# modul_zasilania.net
KiCad netlist of a schematic drawn in EAGLE
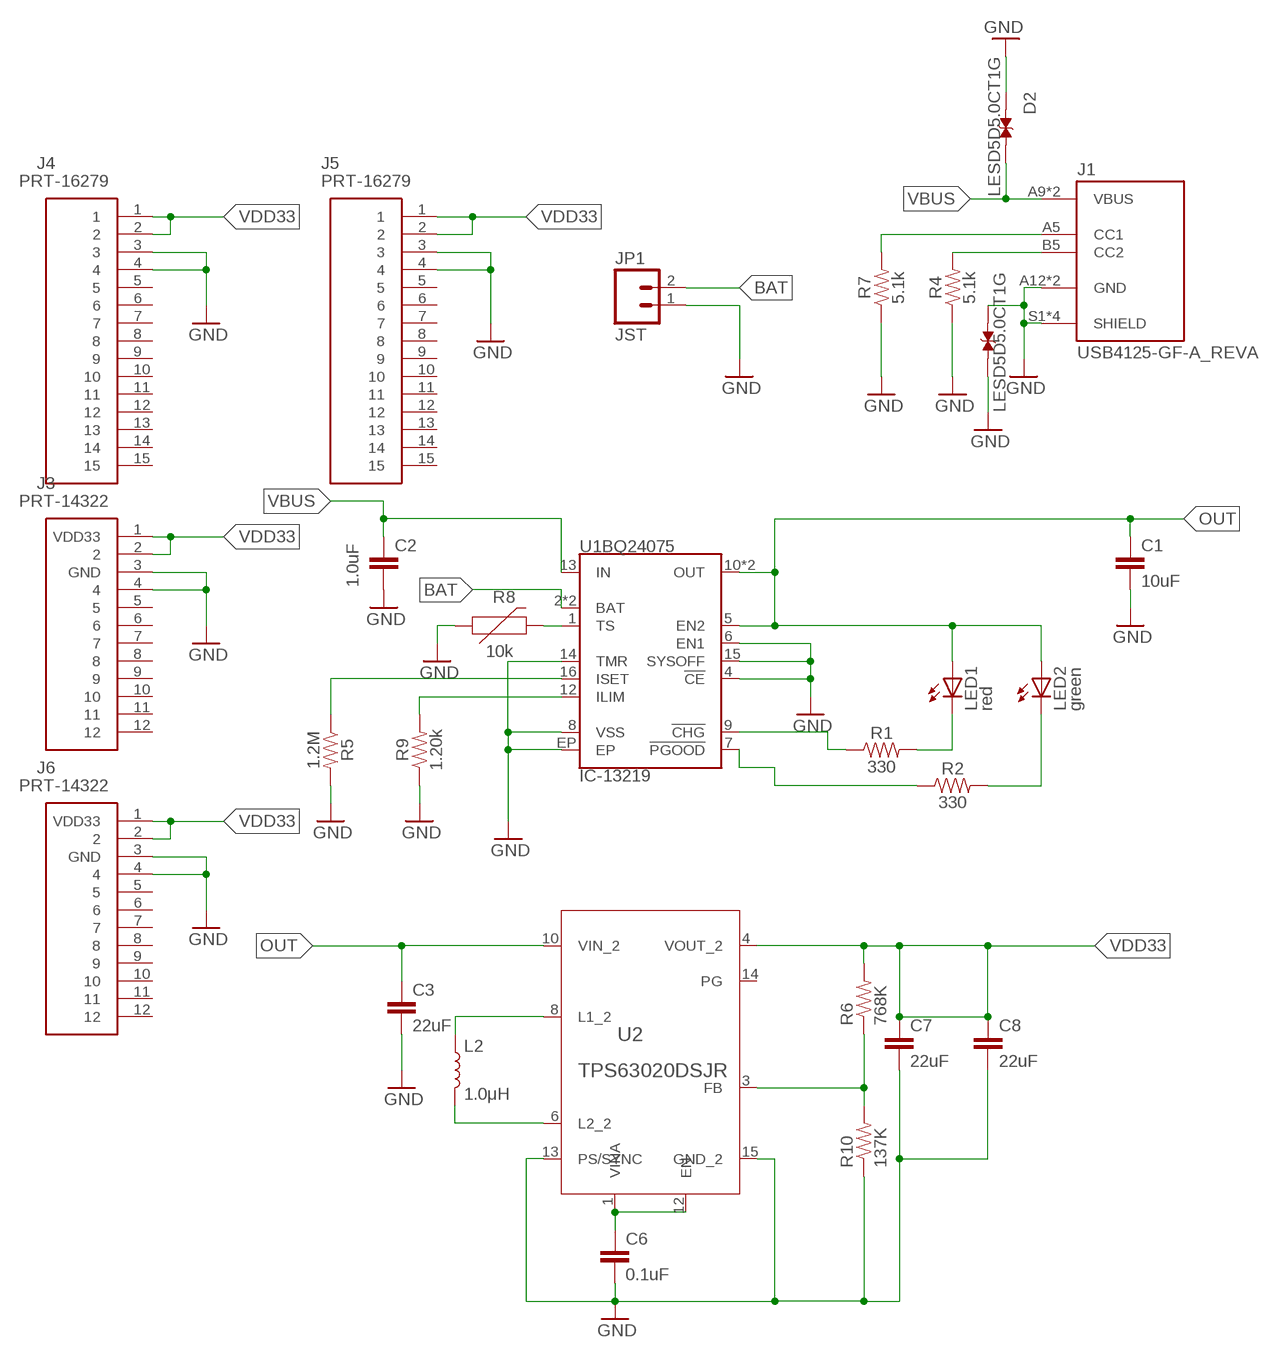
[diagram p0: schematic, sheet 1]

(export (version "E")
  (design (tool "Eeschema 10.0.6"))
  (components
    (comp (ref "C1")
      (value "10uF")
      (footprint "eagle-import:1206")
      (libsource (lib "eagle-import") (part "10UF-1206-6.3V-20%"))
    )
    (comp (ref "C2")
      (value "1.0uF")
      (footprint "eagle-import:0603")
      (libsource (lib "eagle-import") (part "1.0UF-0603-16V-10%"))
    )
    (comp (ref "C3")
      (value "22uF")
      (footprint "eagle-import:0603")
      (libsource (lib "eagle-import") (part "22UF-0603-6.3V-20%"))
    )
    (comp (ref "C6")
      (value "0.1uF")
      (footprint "eagle-import:0402")
      (libsource (lib "eagle-import") (part "0.1UF-0402-16V-10%"))
    )
    (comp (ref "C7")
      (value "22uF")
      (footprint "eagle-import:0603")
      (libsource (lib "eagle-import") (part "22UF-0603-6.3V-20%"))
    )
    (comp (ref "C8")
      (value "22uF")
      (footprint "eagle-import:0603")
      (libsource (lib "eagle-import") (part "22UF-0603-6.3V-20%"))
    )
    (comp (ref "D1")
      (value "LESD5D5.0CT1G")
      (footprint "eagle-import:TVS_LESD5D5.0CT1G")
      (fields (field (name "MF") "Leshan Radio Co."))
      (libsource (lib "eagle-import") (part "LESD5D5.0CT1G"))
    )
    (comp (ref "D2")
      (value "LESD5D5.0CT1G")
      (footprint "eagle-import:TVS_LESD5D5.0CT1G")
      (fields (field (name "MF") "Leshan Radio Co."))
      (libsource (lib "eagle-import") (part "LESD5D5.0CT1G"))
    )
    (comp (ref "J1")
      (value "USB4125-GF-A_REVA")
      (footprint "eagle-import:GCT_USB4125-GF-A_REVA")
      (fields (field (name "MF") "Global Connector Technology") (field (name "MP") "USB4125-GF-A"))
      (libsource (lib "eagle-import") (part "USB4125-GF-A_REVA"))
    )
    (comp (ref "J3")
      (value "PRT-14322")
      (footprint "eagle-import:RHDR12W87P0X254_1X12_3103X250X")
      (fields (field (name "MOUSER_PART_NUMBER") "474-PRT-14322"))
      (libsource (lib "eagle-import") (part "PRT-14322"))
    )
    (comp (ref "J4")
      (value "PRT-16279")
      (footprint "eagle-import:PRT16279")
      (fields (field (name "MOUSER_PART_NUMBER") "474-PRT-16279"))
      (libsource (lib "eagle-import") (part "PRT-16279"))
    )
    (comp (ref "J5")
      (value "PRT-16279")
      (footprint "eagle-import:PRT16279")
      (fields (field (name "MOUSER_PART_NUMBER") "474-PRT-16279"))
      (libsource (lib "eagle-import") (part "PRT-16279"))
    )
    (comp (ref "J6")
      (value "PRT-14322")
      (footprint "eagle-import:RHDR12W87P0X254_1X12_3103X250X")
      (fields (field (name "MOUSER_PART_NUMBER") "474-PRT-14322"))
      (libsource (lib "eagle-import") (part "PRT-14322"))
    )
    (comp (ref "JP1")
      (value "JST")
      (footprint "eagle-import:JST-2-SMD")
      (libsource (lib "eagle-import") (part "M02-JST-2MM-SMT"))
    )
    (comp (ref "L2")
      (value "1.0μH")
      (footprint "eagle-import:0805-WIDE")
      (libsource (lib "eagle-import") (part "1.0μH-0805_WIDE-1.0μH-1.4A-0.07OHM-1.4MM_H"))
    )
    (comp (ref "LED1")
      (value "red")
      (footprint "eagle-import:CHIP-LED0805")
      (libsource (lib "eagle-import") (part "LEDCHIP-LED0805"))
    )
    (comp (ref "LED2")
      (value "green")
      (footprint "eagle-import:CHIP-LED0805")
      (libsource (lib "eagle-import") (part "LEDCHIP-LED0805"))
    )
    (comp (ref "R1")
      (value "330")
      (footprint "eagle-import:0603")
      (libsource (lib "eagle-import") (part "330OHM-0603-1/10W-1%"))
    )
    (comp (ref "R2")
      (value "330")
      (footprint "eagle-import:0603")
      (libsource (lib "eagle-import") (part "330OHM-0603-1/10W-1%"))
    )
    (comp (ref "R4")
      (value "5.1k")
      (footprint "eagle-import:0603")
      (libsource (lib "eagle-import") (part "5.1KOHM5.1KOHM-0603-1/10W-1%"))
    )
    (comp (ref "R5")
      (value "1.2M")
      (footprint "eagle-import:0603")
      (libsource (lib "eagle-import") (part "1.2MOHM-0603-1/10W-1%"))
    )
    (comp (ref "R6")
      (value "768K")
      (footprint "eagle-import:0603")
      (fields
        (field (name "MANUFACTURER") "Vishay Dale")
        (field (name "PART_NUMBER") "CRCW06034K70JNEAHP")
        (field (name "POWER") "0.25W, 1/4W")
      )
      (libsource (lib "eagle-import") (part "CRCW?06034K70JNEAHP"))
    )
    (comp (ref "R7")
      (value "5.1k")
      (footprint "eagle-import:0603")
      (libsource (lib "eagle-import") (part "5.1KOHM5.1KOHM-0603-1/10W-1%"))
    )
    (comp (ref "R8")
      (value "10k")
      (footprint "eagle-import:0603@1")
      (libsource (lib "eagle-import") (part "NTC-THERMISTOR-0603"))
    )
    (comp (ref "R9")
      (value "1.20k")
      (footprint "eagle-import:0603")
      (libsource (lib "eagle-import") (part "1.20KOHM-0603-1/10W-1%"))
    )
    (comp (ref "R10")
      (value "137K")
      (footprint "eagle-import:0603")
      (fields
        (field (name "MANUFACTURER") "Vishay Dale")
        (field (name "PART_NUMBER") "CRCW06034K70JNEAHP")
        (field (name "POWER") "0.25W, 1/4W")
      )
      (libsource (lib "eagle-import") (part "CRCW?06034K70JNEAHP"))
    )
    (comp (ref "U1BQ24075")
      (value "IC-13219")
      (footprint "eagle-import:PVQFN-N16")
      (libsource (lib "eagle-import") (part "BQ24075"))
    )
    (comp (ref "U2")
      (value "TPS63020DSJR")
      (footprint "eagle-import:R-PVSON-N14")
      (libsource (lib "eagle-import") (part "TPS63020DSJR"))
    )
  )
  (nets
    (net (code "1") (name "BAT") (class "Default")
      (node (ref "JP1") (pin "2") (pinfunction "2_2") (pintype "passive"))
      (node (ref "U1BQ24075") (pin "2") (pinfunction "BAT_2") (pintype "bidirectional"))
      (node (ref "U1BQ24075") (pin "3") (pinfunction "BAT_3") (pintype "bidirectional"))
    )
    (net (code "2") (name "GND") (class "Default")
      (node (ref "C1") (pin "2") (pinfunction "2_2") (pintype "passive"))
      (node (ref "C2") (pin "2") (pinfunction "2_2") (pintype "passive"))
      (node (ref "C3") (pin "2") (pinfunction "2_2") (pintype "passive"))
      (node (ref "C6") (pin "2") (pinfunction "2_2") (pintype "passive"))
      (node (ref "C7") (pin "2") (pinfunction "2_2") (pintype "passive"))
      (node (ref "C8") (pin "2") (pinfunction "2_2") (pintype "passive"))
      (node (ref "D1") (pin "1") (pinfunction "1_1") (pintype "passive"))
      (node (ref "D1") (pin "2") (pinfunction "2_2") (pintype "passive"))
      (node (ref "D2") (pin "1") (pinfunction "1_1") (pintype "passive"))
      (node (ref "J1") (pin "A12") (pinfunction "GND_A12") (pintype "power_in"))
      (node (ref "J1") (pin "B12") (pinfunction "GND_B12") (pintype "power_in"))
      (node (ref "J1") (pin "S1") (pinfunction "SHIELD_S1") (pintype "passive"))
      (node (ref "J1") (pin "S2") (pinfunction "SHIELD_S2") (pintype "passive"))
      (node (ref "J1") (pin "S3") (pinfunction "SHIELD_S3") (pintype "passive"))
      (node (ref "J1") (pin "S4") (pinfunction "SHIELD_S4") (pintype "passive"))
      (node (ref "J3") (pin "3") (pinfunction "GND_3") (pintype "bidirectional"))
      (node (ref "J3") (pin "4") (pinfunction "4_4") (pintype "bidirectional"))
      (node (ref "J4") (pin "3") (pinfunction "3_3") (pintype "bidirectional"))
      (node (ref "J4") (pin "4") (pinfunction "4_4") (pintype "bidirectional"))
      (node (ref "J5") (pin "3") (pinfunction "3_3") (pintype "bidirectional"))
      (node (ref "J5") (pin "4") (pinfunction "4_4") (pintype "bidirectional"))
      (node (ref "J6") (pin "3") (pinfunction "GND_3") (pintype "bidirectional"))
      (node (ref "J6") (pin "4") (pinfunction "4_4") (pintype "bidirectional"))
      (node (ref "JP1") (pin "1") (pinfunction "1_1") (pintype "passive"))
      (node (ref "R10") (pin "1") (pinfunction "1_1") (pintype "passive"))
      (node (ref "R4") (pin "1") (pinfunction "1_1") (pintype "passive"))
      (node (ref "R5") (pin "2") (pinfunction "2_2") (pintype "passive"))
      (node (ref "R7") (pin "1") (pinfunction "1_1") (pintype "passive"))
      (node (ref "R8") (pin "1") (pinfunction "1_1") (pintype "bidirectional"))
      (node (ref "R9") (pin "1") (pinfunction "1_1") (pintype "passive"))
      (node (ref "U1BQ24075") (pin "14") (pinfunction "TMR_14") (pintype "bidirectional"))
      (node (ref "U1BQ24075") (pin "15") (pinfunction "SYSOFF_15") (pintype "bidirectional"))
      (node (ref "U1BQ24075") (pin "4") (pinfunction "~{CE}_4") (pintype "bidirectional"))
      (node (ref "U1BQ24075") (pin "6") (pinfunction "EN1_6") (pintype "bidirectional"))
      (node (ref "U1BQ24075") (pin "8") (pinfunction "VSS_8") (pintype "bidirectional"))
      (node (ref "U1BQ24075") (pin "EP") (pinfunction "EP_EP") (pintype "bidirectional"))
      (node (ref "U2") (pin "13") (pinfunction "PS/SYNC_13") (pintype "passive"))
      (node (ref "U2") (pin "15") (pinfunction "GND_2_15") (pintype "passive"))
    )
    (net (code "3") (name "Net-(J1-CC1)") (class "Default")
      (node (ref "J1") (pin "A5") (pinfunction "CC1_A5") (pintype "bidirectional"))
      (node (ref "R7") (pin "2") (pinfunction "2_2") (pintype "passive"))
    )
    (net (code "4") (name "Net-(J1-CC2)") (class "Default")
      (node (ref "J1") (pin "B5") (pinfunction "CC2_B5") (pintype "bidirectional"))
      (node (ref "R4") (pin "2") (pinfunction "2_2") (pintype "passive"))
    )
    (net (code "5") (name "Net-(LED1-PadC)") (class "Default")
      (node (ref "LED1") (pin "C") (pinfunction "C_C") (pintype "passive"))
      (node (ref "R1") (pin "2") (pinfunction "2_2") (pintype "passive"))
    )
    (net (code "6") (name "Net-(LED2-PadC)") (class "Default")
      (node (ref "LED2") (pin "C") (pinfunction "C_C") (pintype "passive"))
      (node (ref "R2") (pin "2") (pinfunction "2_2") (pintype "passive"))
    )
    (net (code "7") (name "Net-(U1BQ24075-ILIM)") (class "Default")
      (node (ref "R9") (pin "2") (pinfunction "2_2") (pintype "passive"))
      (node (ref "U1BQ24075") (pin "12") (pinfunction "ILIM_12") (pintype "bidirectional"))
    )
    (net (code "8") (name "Net-(U1BQ24075-ISET)") (class "Default")
      (node (ref "R5") (pin "1") (pinfunction "1_1") (pintype "passive"))
      (node (ref "U1BQ24075") (pin "16") (pinfunction "ISET_16") (pintype "bidirectional"))
    )
    (net (code "9") (name "Net-(U1BQ24075-TS)") (class "Default")
      (node (ref "R8") (pin "2") (pinfunction "2_2") (pintype "bidirectional"))
      (node (ref "U1BQ24075") (pin "1") (pinfunction "TS_1") (pintype "bidirectional"))
    )
    (net (code "10") (name "Net-(U1BQ24075-~{CHG})") (class "Default")
      (node (ref "R1") (pin "1") (pinfunction "1_1") (pintype "passive"))
      (node (ref "U1BQ24075") (pin "9") (pinfunction "~{CHG}_9") (pintype "bidirectional"))
    )
    (net (code "11") (name "Net-(U1BQ24075-~{PGOOD})") (class "Default")
      (node (ref "R2") (pin "1") (pinfunction "1_1") (pintype "passive"))
      (node (ref "U1BQ24075") (pin "7") (pinfunction "~{PGOOD}_7") (pintype "bidirectional"))
    )
    (net (code "12") (name "Net-(U2-EN)") (class "Default")
      (node (ref "C6") (pin "1") (pinfunction "1_1") (pintype "passive"))
      (node (ref "U2") (pin "1") (pinfunction "VINA_1") (pintype "passive"))
      (node (ref "U2") (pin "12") (pinfunction "EN_12") (pintype "passive"))
    )
    (net (code "13") (name "Net-(U2-FB)") (class "Default")
      (node (ref "R10") (pin "2") (pinfunction "2_2") (pintype "passive"))
      (node (ref "R6") (pin "1") (pinfunction "1_1") (pintype "passive"))
      (node (ref "U2") (pin "3") (pinfunction "FB_3") (pintype "passive"))
    )
    (net (code "14") (name "Net-(U2-L1_2)") (class "Default")
      (node (ref "L2") (pin "1") (pinfunction "1_1") (pintype "passive"))
      (node (ref "U2") (pin "8") (pinfunction "L1_2_8") (pintype "passive"))
    )
    (net (code "15") (name "Net-(U2-L2_2)") (class "Default")
      (node (ref "L2") (pin "2") (pinfunction "2_2") (pintype "passive"))
      (node (ref "U2") (pin "6") (pinfunction "L2_2_6") (pintype "passive"))
    )
    (net (code "16") (name "OUT") (class "Default")
      (node (ref "C1") (pin "1") (pinfunction "1_1") (pintype "passive"))
      (node (ref "C3") (pin "1") (pinfunction "1_1") (pintype "passive"))
      (node (ref "LED1") (pin "A") (pinfunction "A_A") (pintype "passive"))
      (node (ref "LED2") (pin "A") (pinfunction "A_A") (pintype "passive"))
      (node (ref "U1BQ24075") (pin "10") (pinfunction "OUT_10") (pintype "bidirectional"))
      (node (ref "U1BQ24075") (pin "11") (pinfunction "OUT_11") (pintype "bidirectional"))
      (node (ref "U1BQ24075") (pin "5") (pinfunction "EN2_5") (pintype "bidirectional"))
      (node (ref "U2") (pin "10") (pinfunction "VIN_2_10") (pintype "passive"))
    )
    (net (code "17") (name "VBUS") (class "Default")
      (node (ref "C2") (pin "1") (pinfunction "1_1") (pintype "passive"))
      (node (ref "D2") (pin "2") (pinfunction "2_2") (pintype "passive"))
      (node (ref "J1") (pin "A9") (pinfunction "VBUS_A9") (pintype "power_in"))
      (node (ref "J1") (pin "B9") (pinfunction "VBUS_B9") (pintype "power_in"))
      (node (ref "U1BQ24075") (pin "13") (pinfunction "IN_13") (pintype "bidirectional"))
    )
    (net (code "18") (name "VDD33") (class "Default")
      (node (ref "C7") (pin "1") (pinfunction "1_1") (pintype "passive"))
      (node (ref "C8") (pin "1") (pinfunction "1_1") (pintype "passive"))
      (node (ref "J3") (pin "1") (pinfunction "VDD33_1") (pintype "bidirectional"))
      (node (ref "J3") (pin "2") (pinfunction "2_2") (pintype "bidirectional"))
      (node (ref "J4") (pin "1") (pinfunction "1_1") (pintype "bidirectional"))
      (node (ref "J4") (pin "2") (pinfunction "2_2") (pintype "bidirectional"))
      (node (ref "J5") (pin "1") (pinfunction "1_1") (pintype "bidirectional"))
      (node (ref "J5") (pin "2") (pinfunction "2_2") (pintype "bidirectional"))
      (node (ref "J6") (pin "1") (pinfunction "VDD33_1") (pintype "bidirectional"))
      (node (ref "J6") (pin "2") (pinfunction "2_2") (pintype "bidirectional"))
      (node (ref "R6") (pin "2") (pinfunction "2_2") (pintype "passive"))
      (node (ref "U2") (pin "4") (pinfunction "VOUT_2_4") (pintype "passive"))
    )
    (net (code "19") (name "unconnected-(J3-Pad5)") (class "Default")
      (node (ref "J3") (pin "5") (pinfunction "5_5") (pintype "bidirectional"))
    )
    (net (code "20") (name "unconnected-(J3-Pad6)") (class "Default")
      (node (ref "J3") (pin "6") (pinfunction "6_6") (pintype "bidirectional"))
    )
    (net (code "21") (name "unconnected-(J3-Pad7)") (class "Default")
      (node (ref "J3") (pin "7") (pinfunction "7_7") (pintype "bidirectional"))
    )
    (net (code "22") (name "unconnected-(J3-Pad8)") (class "Default")
      (node (ref "J3") (pin "8") (pinfunction "8_8") (pintype "bidirectional"))
    )
    (net (code "23") (name "unconnected-(J3-Pad9)") (class "Default")
      (node (ref "J3") (pin "9") (pinfunction "9_9") (pintype "bidirectional"))
    )
    (net (code "24") (name "unconnected-(J3-Pad10)") (class "Default")
      (node (ref "J3") (pin "10") (pinfunction "10_10") (pintype "bidirectional"))
    )
    (net (code "25") (name "unconnected-(J3-Pad11)") (class "Default")
      (node (ref "J3") (pin "11") (pinfunction "11_11") (pintype "bidirectional"))
    )
    (net (code "26") (name "unconnected-(J3-Pad12)") (class "Default")
      (node (ref "J3") (pin "12") (pinfunction "12_12") (pintype "bidirectional"))
    )
    (net (code "27") (name "unconnected-(J4-Pad5)") (class "Default")
      (node (ref "J4") (pin "5") (pinfunction "5_5") (pintype "bidirectional"))
    )
    (net (code "28") (name "unconnected-(J4-Pad6)") (class "Default")
      (node (ref "J4") (pin "6") (pinfunction "6_6") (pintype "bidirectional"))
    )
    (net (code "29") (name "unconnected-(J4-Pad7)") (class "Default")
      (node (ref "J4") (pin "7") (pinfunction "7_7") (pintype "bidirectional"))
    )
    (net (code "30") (name "unconnected-(J4-Pad8)") (class "Default")
      (node (ref "J4") (pin "8") (pinfunction "8_8") (pintype "bidirectional"))
    )
    (net (code "31") (name "unconnected-(J4-Pad9)") (class "Default")
      (node (ref "J4") (pin "9") (pinfunction "9_9") (pintype "bidirectional"))
    )
    (net (code "32") (name "unconnected-(J4-Pad10)") (class "Default")
      (node (ref "J4") (pin "10") (pinfunction "10_10") (pintype "bidirectional"))
    )
    (net (code "33") (name "unconnected-(J4-Pad11)") (class "Default")
      (node (ref "J4") (pin "11") (pinfunction "11_11") (pintype "bidirectional"))
    )
    (net (code "34") (name "unconnected-(J4-Pad12)") (class "Default")
      (node (ref "J4") (pin "12") (pinfunction "12_12") (pintype "bidirectional"))
    )
    (net (code "35") (name "unconnected-(J4-Pad13)") (class "Default")
      (node (ref "J4") (pin "13") (pinfunction "13_13") (pintype "bidirectional"))
    )
    (net (code "36") (name "unconnected-(J4-Pad14)") (class "Default")
      (node (ref "J4") (pin "14") (pinfunction "14_14") (pintype "bidirectional"))
    )
    (net (code "37") (name "unconnected-(J4-Pad15)") (class "Default")
      (node (ref "J4") (pin "15") (pinfunction "15_15") (pintype "bidirectional"))
    )
    (net (code "38") (name "unconnected-(J5-Pad5)") (class "Default")
      (node (ref "J5") (pin "5") (pinfunction "5_5") (pintype "bidirectional"))
    )
    (net (code "39") (name "unconnected-(J5-Pad6)") (class "Default")
      (node (ref "J5") (pin "6") (pinfunction "6_6") (pintype "bidirectional"))
    )
    (net (code "40") (name "unconnected-(J5-Pad7)") (class "Default")
      (node (ref "J5") (pin "7") (pinfunction "7_7") (pintype "bidirectional"))
    )
    (net (code "41") (name "unconnected-(J5-Pad8)") (class "Default")
      (node (ref "J5") (pin "8") (pinfunction "8_8") (pintype "bidirectional"))
    )
    (net (code "42") (name "unconnected-(J5-Pad9)") (class "Default")
      (node (ref "J5") (pin "9") (pinfunction "9_9") (pintype "bidirectional"))
    )
    (net (code "43") (name "unconnected-(J5-Pad10)") (class "Default")
      (node (ref "J5") (pin "10") (pinfunction "10_10") (pintype "bidirectional"))
    )
    (net (code "44") (name "unconnected-(J5-Pad11)") (class "Default")
      (node (ref "J5") (pin "11") (pinfunction "11_11") (pintype "bidirectional"))
    )
    (net (code "45") (name "unconnected-(J5-Pad12)") (class "Default")
      (node (ref "J5") (pin "12") (pinfunction "12_12") (pintype "bidirectional"))
    )
    (net (code "46") (name "unconnected-(J5-Pad13)") (class "Default")
      (node (ref "J5") (pin "13") (pinfunction "13_13") (pintype "bidirectional"))
    )
    (net (code "47") (name "unconnected-(J5-Pad14)") (class "Default")
      (node (ref "J5") (pin "14") (pinfunction "14_14") (pintype "bidirectional"))
    )
    (net (code "48") (name "unconnected-(J5-Pad15)") (class "Default")
      (node (ref "J5") (pin "15") (pinfunction "15_15") (pintype "bidirectional"))
    )
    (net (code "49") (name "unconnected-(J6-Pad5)") (class "Default")
      (node (ref "J6") (pin "5") (pinfunction "5_5") (pintype "bidirectional"))
    )
    (net (code "50") (name "unconnected-(J6-Pad6)") (class "Default")
      (node (ref "J6") (pin "6") (pinfunction "6_6") (pintype "bidirectional"))
    )
    (net (code "51") (name "unconnected-(J6-Pad7)") (class "Default")
      (node (ref "J6") (pin "7") (pinfunction "7_7") (pintype "bidirectional"))
    )
    (net (code "52") (name "unconnected-(J6-Pad8)") (class "Default")
      (node (ref "J6") (pin "8") (pinfunction "8_8") (pintype "bidirectional"))
    )
    (net (code "53") (name "unconnected-(J6-Pad9)") (class "Default")
      (node (ref "J6") (pin "9") (pinfunction "9_9") (pintype "bidirectional"))
    )
    (net (code "54") (name "unconnected-(J6-Pad10)") (class "Default")
      (node (ref "J6") (pin "10") (pinfunction "10_10") (pintype "bidirectional"))
    )
    (net (code "55") (name "unconnected-(J6-Pad11)") (class "Default")
      (node (ref "J6") (pin "11") (pinfunction "11_11") (pintype "bidirectional"))
    )
    (net (code "56") (name "unconnected-(J6-Pad12)") (class "Default")
      (node (ref "J6") (pin "12") (pinfunction "12_12") (pintype "bidirectional"))
    )
    (net (code "57") (name "unconnected-(U2-PG-Pad14)") (class "Default")
      (node (ref "U2") (pin "14") (pinfunction "PG_14") (pintype "passive"))
    )
  )
)
